# interface.net
KiCad netlist of a schematic drawn in EAGLE
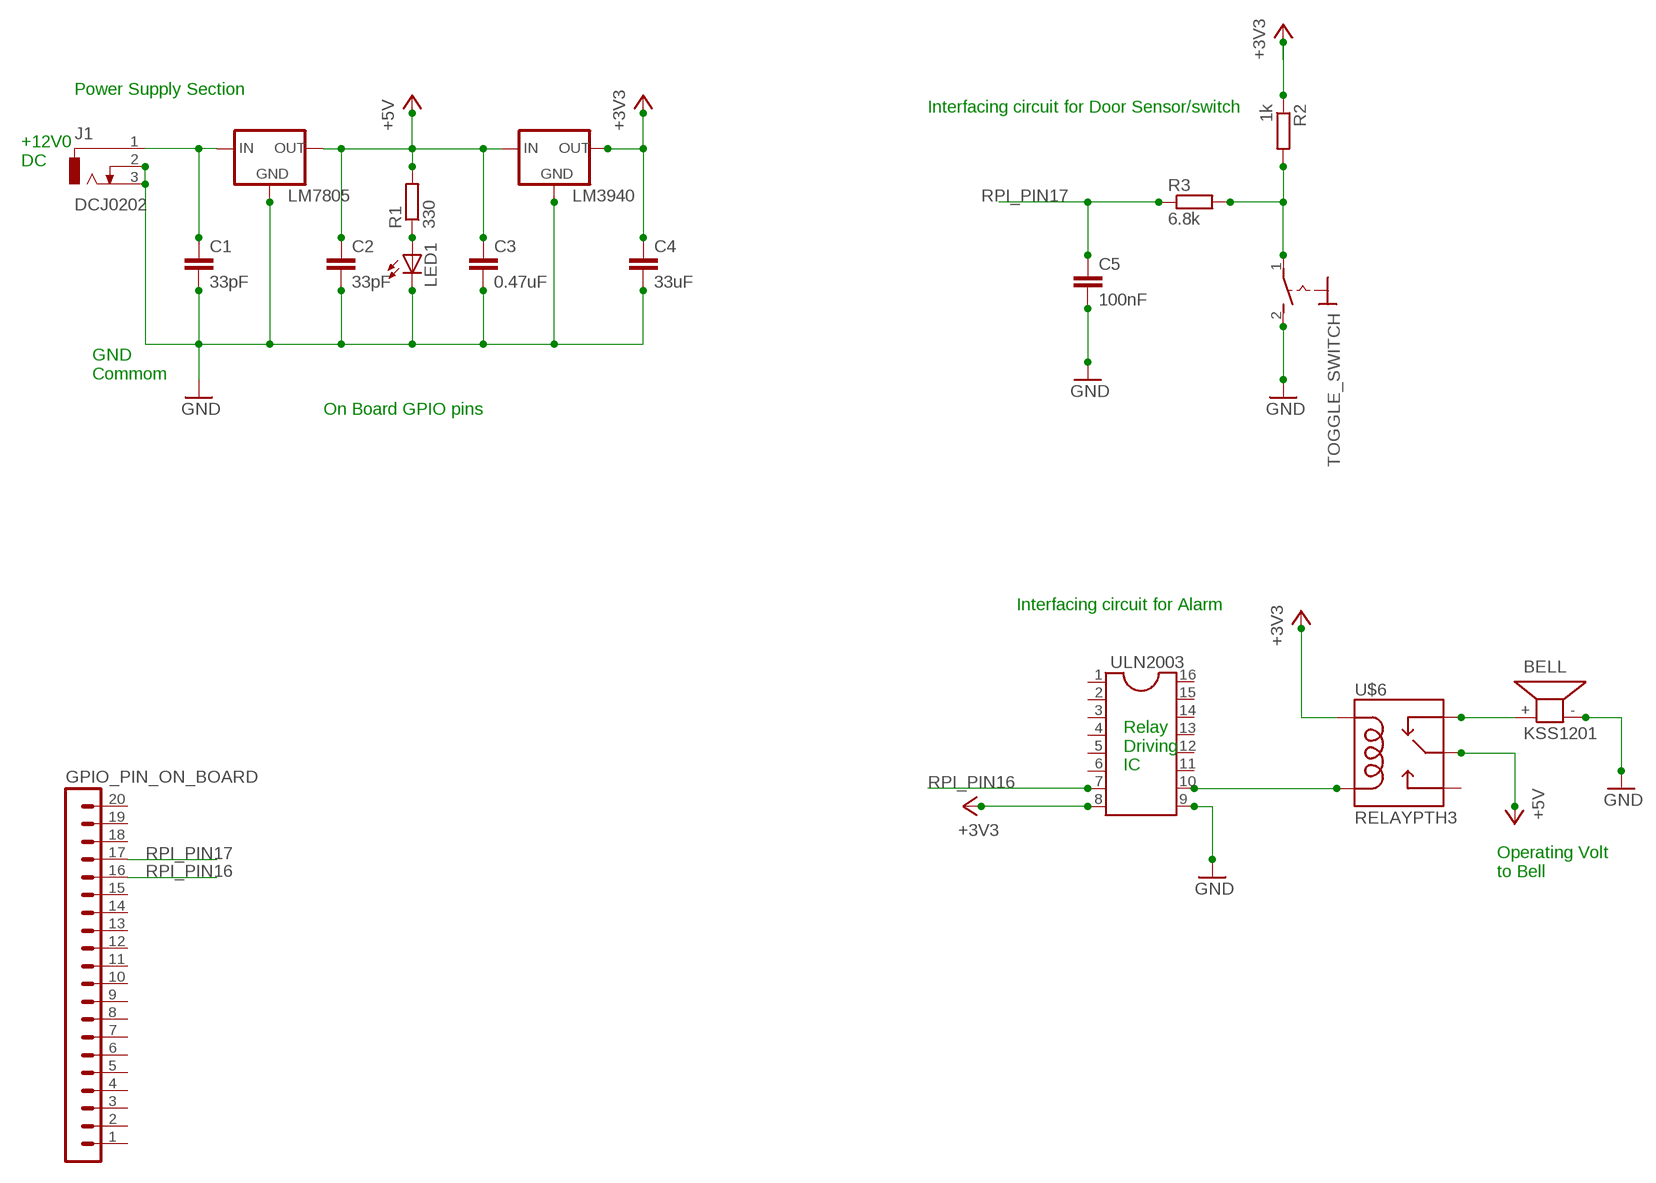
[diagram p0: schematic, sheet 1]

(export (version "E")
  (design (tool "Eeschema 10.0.6"))
  (components
    (comp (ref "BELL")
      (value "KSS1201")
      (footprint "eagle-import:KSS1201")
      (libsource (lib "eagle-import") (part "KSS1201"))
    )
    (comp (ref "C1")
      (value "33pF")
      (footprint "eagle-import:C025-025X050")
      (libsource (lib "eagle-import") (part "C-EU025-025X050"))
    )
    (comp (ref "C2")
      (value "33pF")
      (footprint "eagle-import:C025-025X050")
      (libsource (lib "eagle-import") (part "C-EU025-025X050"))
    )
    (comp (ref "C3")
      (value "0.47uF")
      (footprint "eagle-import:C025-025X050")
      (libsource (lib "eagle-import") (part "C-EU025-025X050"))
    )
    (comp (ref "C4")
      (value "33uF")
      (footprint "eagle-import:C025-025X050")
      (libsource (lib "eagle-import") (part "C-EU025-025X050"))
    )
    (comp (ref "C5")
      (value "100nF")
      (footprint "eagle-import:C025-025X050")
      (libsource (lib "eagle-import") (part "C-EU025-025X050"))
    )
    (comp (ref "GPIO_PIN_ON_BOARD")
      (value "MA20-1")
      (footprint "eagle-import:MA20-1")
      (libsource (lib "eagle-import") (part "MA20-1"))
    )
    (comp (ref "J1")
      (value "DCJ0202")
      (footprint "eagle-import:DCJ0202")
      (libsource (lib "eagle-import") (part "DCJ0202"))
    )
    (comp (ref "LED1")
      (value "LED3MM")
      (footprint "eagle-import:LED3MM")
      (libsource (lib "eagle-import") (part "LED3MM"))
    )
    (comp (ref "LM3940")
      (value "78XXL")
      (footprint "eagle-import:78XXL")
      (libsource (lib "eagle-import") (part "78XXL"))
    )
    (comp (ref "LM7805")
      (value "78XXL")
      (footprint "eagle-import:78XXL")
      (libsource (lib "eagle-import") (part "78XXL"))
    )
    (comp (ref "R1")
      (value "330")
      (footprint "eagle-import:0207_7")
      (libsource (lib "eagle-import") (part "R-EU_0207/7"))
    )
    (comp (ref "R2")
      (value "1k")
      (footprint "eagle-import:0207_7")
      (libsource (lib "eagle-import") (part "R-EU_0207/7"))
    )
    (comp (ref "R3")
      (value "6.8k")
      (footprint "eagle-import:0207_7")
      (libsource (lib "eagle-import") (part "R-EU_0207/7"))
    )
    (comp (ref "TOGGLE_SWITCH")
      (value "MS243")
      (footprint "eagle-import:MS243")
      (libsource (lib "eagle-import") (part "MS243"))
    )
    (comp (ref "U$6")
      (value "RELAYPTH3")
      (footprint "eagle-import:RELAY-T9A-2")
      (libsource (lib "eagle-import") (part "RELAYPTH3"))
    )
    (comp (ref "ULN2003")
      (value "DIL16")
      (footprint "eagle-import:DIL16")
      (libsource (lib "eagle-import") (part "DIL16"))
    )
  )
  (nets
    (net (code "1") (name "+3V3") (class "Default")
      (node (ref "C4") (pin "1") (pinfunction "1_1") (pintype "passive"))
      (node (ref "LM3940") (pin "OUT") (pinfunction "OUT_OUT") (pintype "passive"))
      (node (ref "R2") (pin "1") (pinfunction "1_1") (pintype "passive"))
      (node (ref "U$6") (pin "COIL1") (pinfunction "COIL1_COIL1") (pintype "bidirectional"))
      (node (ref "ULN2003") (pin "8") (pinfunction "8_8") (pintype "passive"))
    )
    (net (code "2") (name "+5V") (class "Default")
      (node (ref "C2") (pin "1") (pinfunction "1_1") (pintype "passive"))
      (node (ref "C3") (pin "1") (pinfunction "1_1") (pintype "passive"))
      (node (ref "LM3940") (pin "IN") (pinfunction "IN_IN") (pintype "input"))
      (node (ref "LM7805") (pin "OUT") (pinfunction "OUT_OUT") (pintype "passive"))
      (node (ref "R1") (pin "2") (pinfunction "2_2") (pintype "passive"))
      (node (ref "U$6") (pin "MAIN") (pinfunction "MAIN_MAIN") (pintype "bidirectional"))
    )
    (net (code "3") (name "/RPI_PIN16") (class "Default")
      (node (ref "GPIO_PIN_ON_BOARD") (pin "16") (pinfunction "16_16") (pintype "passive"))
      (node (ref "ULN2003") (pin "7") (pinfunction "7_7") (pintype "passive"))
    )
    (net (code "4") (name "/RPI_PIN17") (class "Default")
      (node (ref "C5") (pin "1") (pinfunction "1_1") (pintype "passive"))
      (node (ref "GPIO_PIN_ON_BOARD") (pin "17") (pinfunction "17_17") (pintype "passive"))
      (node (ref "R3") (pin "1") (pinfunction "1_1") (pintype "passive"))
    )
    (net (code "5") (name "GND") (class "Default")
      (node (ref "BELL") (pin "-") (pinfunction "2_-") (pintype "passive"))
      (node (ref "C1") (pin "2") (pinfunction "2_2") (pintype "passive"))
      (node (ref "C2") (pin "2") (pinfunction "2_2") (pintype "passive"))
      (node (ref "C3") (pin "2") (pinfunction "2_2") (pintype "passive"))
      (node (ref "C4") (pin "2") (pinfunction "2_2") (pintype "passive"))
      (node (ref "C5") (pin "2") (pinfunction "2_2") (pintype "passive"))
      (node (ref "J1") (pin "2") (pinfunction "2_2") (pintype "passive"))
      (node (ref "J1") (pin "3") (pinfunction "3_3") (pintype "passive"))
      (node (ref "LED1") (pin "K") (pinfunction "C_K") (pintype "passive"))
      (node (ref "LM3940") (pin "GND") (pinfunction "GND_GND") (pintype "input"))
      (node (ref "LM7805") (pin "GND") (pinfunction "GND_GND") (pintype "input"))
      (node (ref "TOGGLE_SWITCH") (pin "2") (pinfunction "S_2") (pintype "passive"))
      (node (ref "ULN2003") (pin "9") (pinfunction "9_9") (pintype "passive"))
    )
    (net (code "6") (name "Net-(BELL-1)") (class "Default")
      (node (ref "BELL") (pin "+") (pinfunction "1_+") (pintype "passive"))
      (node (ref "U$6") (pin "NC") (pinfunction "NC_NC") (pintype "bidirectional"))
    )
    (net (code "7") (name "Net-(C1-Pad1)") (class "Default")
      (node (ref "C1") (pin "1") (pinfunction "1_1") (pintype "passive"))
      (node (ref "J1") (pin "1") (pinfunction "1_1") (pintype "passive"))
      (node (ref "LM7805") (pin "IN") (pinfunction "IN_IN") (pintype "input"))
    )
    (net (code "8") (name "Net-(LED1-PadA)") (class "Default")
      (node (ref "LED1") (pin "A") (pinfunction "A_A") (pintype "passive"))
      (node (ref "R1") (pin "1") (pinfunction "1_1") (pintype "passive"))
    )
    (net (code "9") (name "Net-(TOGGLE_SWITCH-P)") (class "Default")
      (node (ref "R2") (pin "2") (pinfunction "2_2") (pintype "passive"))
      (node (ref "R3") (pin "2") (pinfunction "2_2") (pintype "passive"))
      (node (ref "TOGGLE_SWITCH") (pin "1") (pinfunction "P_1") (pintype "passive"))
    )
    (net (code "10") (name "Net-(U$6-PadCOIL2)") (class "Default")
      (node (ref "U$6") (pin "COIL2") (pinfunction "COIL2_COIL2") (pintype "bidirectional"))
      (node (ref "ULN2003") (pin "10") (pinfunction "10_10") (pintype "passive"))
    )
    (net (code "11") (name "unconnected-(GPIO_PIN_ON_BOARD-Pad1)") (class "Default")
      (node (ref "GPIO_PIN_ON_BOARD") (pin "1") (pinfunction "1_1") (pintype "passive"))
    )
    (net (code "12") (name "unconnected-(GPIO_PIN_ON_BOARD-Pad2)") (class "Default")
      (node (ref "GPIO_PIN_ON_BOARD") (pin "2") (pinfunction "2_2") (pintype "passive"))
    )
    (net (code "13") (name "unconnected-(GPIO_PIN_ON_BOARD-Pad3)") (class "Default")
      (node (ref "GPIO_PIN_ON_BOARD") (pin "3") (pinfunction "3_3") (pintype "passive"))
    )
    (net (code "14") (name "unconnected-(GPIO_PIN_ON_BOARD-Pad4)") (class "Default")
      (node (ref "GPIO_PIN_ON_BOARD") (pin "4") (pinfunction "4_4") (pintype "passive"))
    )
    (net (code "15") (name "unconnected-(GPIO_PIN_ON_BOARD-Pad5)") (class "Default")
      (node (ref "GPIO_PIN_ON_BOARD") (pin "5") (pinfunction "5_5") (pintype "passive"))
    )
    (net (code "16") (name "unconnected-(GPIO_PIN_ON_BOARD-Pad6)") (class "Default")
      (node (ref "GPIO_PIN_ON_BOARD") (pin "6") (pinfunction "6_6") (pintype "passive"))
    )
    (net (code "17") (name "unconnected-(GPIO_PIN_ON_BOARD-Pad7)") (class "Default")
      (node (ref "GPIO_PIN_ON_BOARD") (pin "7") (pinfunction "7_7") (pintype "passive"))
    )
    (net (code "18") (name "unconnected-(GPIO_PIN_ON_BOARD-Pad8)") (class "Default")
      (node (ref "GPIO_PIN_ON_BOARD") (pin "8") (pinfunction "8_8") (pintype "passive"))
    )
    (net (code "19") (name "unconnected-(GPIO_PIN_ON_BOARD-Pad9)") (class "Default")
      (node (ref "GPIO_PIN_ON_BOARD") (pin "9") (pinfunction "9_9") (pintype "passive"))
    )
    (net (code "20") (name "unconnected-(GPIO_PIN_ON_BOARD-Pad10)") (class "Default")
      (node (ref "GPIO_PIN_ON_BOARD") (pin "10") (pinfunction "10_10") (pintype "passive"))
    )
    (net (code "21") (name "unconnected-(GPIO_PIN_ON_BOARD-Pad11)") (class "Default")
      (node (ref "GPIO_PIN_ON_BOARD") (pin "11") (pinfunction "11_11") (pintype "passive"))
    )
    (net (code "22") (name "unconnected-(GPIO_PIN_ON_BOARD-Pad12)") (class "Default")
      (node (ref "GPIO_PIN_ON_BOARD") (pin "12") (pinfunction "12_12") (pintype "passive"))
    )
    (net (code "23") (name "unconnected-(GPIO_PIN_ON_BOARD-Pad13)") (class "Default")
      (node (ref "GPIO_PIN_ON_BOARD") (pin "13") (pinfunction "13_13") (pintype "passive"))
    )
    (net (code "24") (name "unconnected-(GPIO_PIN_ON_BOARD-Pad14)") (class "Default")
      (node (ref "GPIO_PIN_ON_BOARD") (pin "14") (pinfunction "14_14") (pintype "passive"))
    )
    (net (code "25") (name "unconnected-(GPIO_PIN_ON_BOARD-Pad15)") (class "Default")
      (node (ref "GPIO_PIN_ON_BOARD") (pin "15") (pinfunction "15_15") (pintype "passive"))
    )
    (net (code "26") (name "unconnected-(GPIO_PIN_ON_BOARD-Pad18)") (class "Default")
      (node (ref "GPIO_PIN_ON_BOARD") (pin "18") (pinfunction "18_18") (pintype "passive"))
    )
    (net (code "27") (name "unconnected-(GPIO_PIN_ON_BOARD-Pad19)") (class "Default")
      (node (ref "GPIO_PIN_ON_BOARD") (pin "19") (pinfunction "19_19") (pintype "passive"))
    )
    (net (code "28") (name "unconnected-(GPIO_PIN_ON_BOARD-Pad20)") (class "Default")
      (node (ref "GPIO_PIN_ON_BOARD") (pin "20") (pinfunction "20_20") (pintype "passive"))
    )
    (net (code "29") (name "unconnected-(U$6-PadNO)") (class "Default")
      (node (ref "U$6") (pin "NO") (pinfunction "NO_NO") (pintype "bidirectional"))
    )
    (net (code "30") (name "unconnected-(ULN2003-Pad1)") (class "Default")
      (node (ref "ULN2003") (pin "1") (pinfunction "1_1") (pintype "passive"))
    )
    (net (code "31") (name "unconnected-(ULN2003-Pad2)") (class "Default")
      (node (ref "ULN2003") (pin "2") (pinfunction "2_2") (pintype "passive"))
    )
    (net (code "32") (name "unconnected-(ULN2003-Pad3)") (class "Default")
      (node (ref "ULN2003") (pin "3") (pinfunction "3_3") (pintype "passive"))
    )
    (net (code "33") (name "unconnected-(ULN2003-Pad4)") (class "Default")
      (node (ref "ULN2003") (pin "4") (pinfunction "4_4") (pintype "passive"))
    )
    (net (code "34") (name "unconnected-(ULN2003-Pad5)") (class "Default")
      (node (ref "ULN2003") (pin "5") (pinfunction "5_5") (pintype "passive"))
    )
    (net (code "35") (name "unconnected-(ULN2003-Pad6)") (class "Default")
      (node (ref "ULN2003") (pin "6") (pinfunction "6_6") (pintype "passive"))
    )
    (net (code "36") (name "unconnected-(ULN2003-Pad11)") (class "Default")
      (node (ref "ULN2003") (pin "11") (pinfunction "11_11") (pintype "passive"))
    )
    (net (code "37") (name "unconnected-(ULN2003-Pad12)") (class "Default")
      (node (ref "ULN2003") (pin "12") (pinfunction "12_12") (pintype "passive"))
    )
    (net (code "38") (name "unconnected-(ULN2003-Pad13)") (class "Default")
      (node (ref "ULN2003") (pin "13") (pinfunction "13_13") (pintype "passive"))
    )
    (net (code "39") (name "unconnected-(ULN2003-Pad14)") (class "Default")
      (node (ref "ULN2003") (pin "14") (pinfunction "14_14") (pintype "passive"))
    )
    (net (code "40") (name "unconnected-(ULN2003-Pad15)") (class "Default")
      (node (ref "ULN2003") (pin "15") (pinfunction "15_15") (pintype "passive"))
    )
    (net (code "41") (name "unconnected-(ULN2003-Pad16)") (class "Default")
      (node (ref "ULN2003") (pin "16") (pinfunction "16_16") (pintype "passive"))
    )
  )
)
